# 130816_AriloRX_0_0.net
KiCad netlist of a schematic drawn in EAGLE
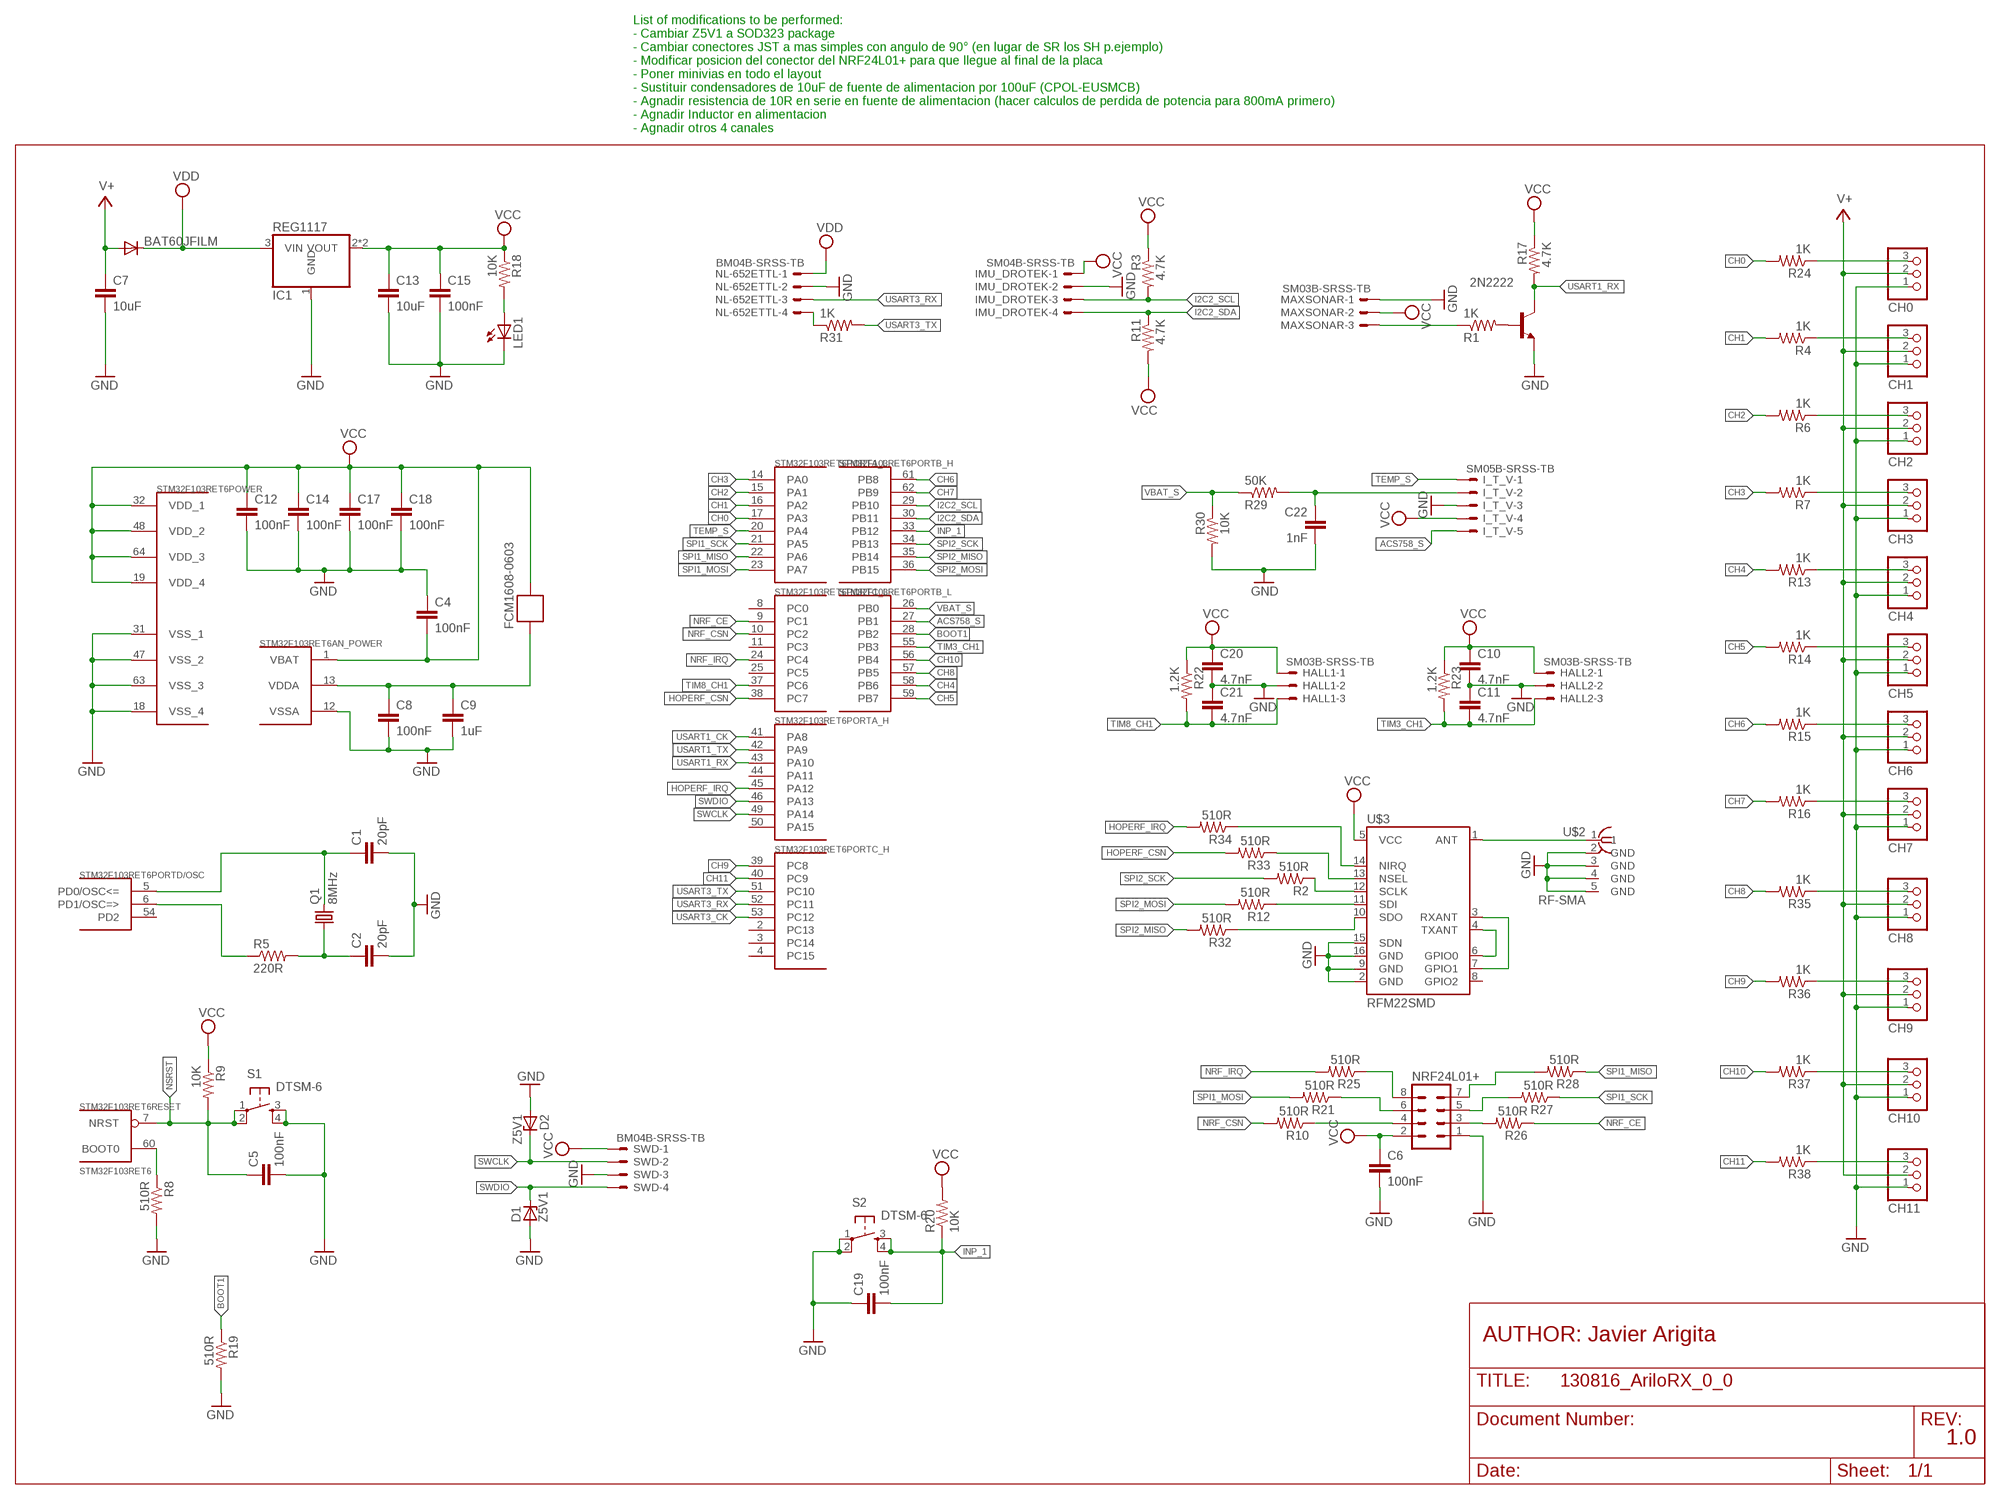
[diagram p0: schematic, sheet 1]

(export (version "E")
  (design (tool "Eeschema 10.0.6"))
  (components
    (comp (ref "2N2222")
      (value "MMBT2222ALT1-NPN-SOT23-BEC")
      (footprint "eagle-import:SOT23-BEC")
      (libsource (lib "eagle-import") (part "-NPN-SOT23-BECMMBT2222ALT1"))
    )
    (comp (ref "BAT60JFILM")
      (value "DIODE-SOD323-R")
      (footprint "eagle-import:SOD323-R")
      (libsource (lib "eagle-import") (part "DIODE-SOD323-R"))
    )
    (comp (ref "C1")
      (value "20pF")
      (footprint "eagle-import:C0805")
      (libsource (lib "eagle-import") (part "C-EUC0805"))
    )
    (comp (ref "C2")
      (value "20pF")
      (footprint "eagle-import:C0805")
      (libsource (lib "eagle-import") (part "C-EUC0805"))
    )
    (comp (ref "C4")
      (value "100nF")
      (footprint "eagle-import:C0805")
      (libsource (lib "eagle-import") (part "C-EUC0805"))
    )
    (comp (ref "C5")
      (value "100nF")
      (footprint "eagle-import:C0805")
      (libsource (lib "eagle-import") (part "C-EUC0805"))
    )
    (comp (ref "C6")
      (value "100nF")
      (footprint "eagle-import:C0805")
      (libsource (lib "eagle-import") (part "C-EUC0805"))
    )
    (comp (ref "C7")
      (value "10uF")
      (footprint "eagle-import:C3216")
      (libsource (lib "eagle-import") (part "resistor_C-EUC3216"))
    )
    (comp (ref "C8")
      (value "100nF")
      (footprint "eagle-import:C0805")
      (libsource (lib "eagle-import") (part "C-EUC0805"))
    )
    (comp (ref "C9")
      (value "1uF")
      (footprint "eagle-import:C3216")
      (libsource (lib "eagle-import") (part "resistor_C-EUC3216"))
    )
    (comp (ref "C10")
      (value "4.7nF")
      (footprint "eagle-import:C0805")
      (libsource (lib "eagle-import") (part "C-EUC0805"))
    )
    (comp (ref "C11")
      (value "4.7nF")
      (footprint "eagle-import:C0805")
      (libsource (lib "eagle-import") (part "C-EUC0805"))
    )
    (comp (ref "C12")
      (value "100nF")
      (footprint "eagle-import:C0805")
      (libsource (lib "eagle-import") (part "C-EUC0805"))
    )
    (comp (ref "C13")
      (value "10uF")
      (footprint "eagle-import:C3216")
      (libsource (lib "eagle-import") (part "resistor_C-EUC3216"))
    )
    (comp (ref "C14")
      (value "100nF")
      (footprint "eagle-import:C0805")
      (libsource (lib "eagle-import") (part "C-EUC0805"))
    )
    (comp (ref "C15")
      (value "100nF")
      (footprint "eagle-import:C0805")
      (libsource (lib "eagle-import") (part "C-EUC0805"))
    )
    (comp (ref "C17")
      (value "100nF")
      (footprint "eagle-import:C0805")
      (libsource (lib "eagle-import") (part "C-EUC0805"))
    )
    (comp (ref "C18")
      (value "100nF")
      (footprint "eagle-import:C0805")
      (libsource (lib "eagle-import") (part "C-EUC0805"))
    )
    (comp (ref "C19")
      (value "100nF")
      (footprint "eagle-import:C0805")
      (libsource (lib "eagle-import") (part "C-EUC0805"))
    )
    (comp (ref "C20")
      (value "4.7nF")
      (footprint "eagle-import:C0805")
      (libsource (lib "eagle-import") (part "C-EUC0805"))
    )
    (comp (ref "C21")
      (value "4.7nF")
      (footprint "eagle-import:C0805")
      (libsource (lib "eagle-import") (part "C-EUC0805"))
    )
    (comp (ref "C22")
      (value "1nF")
      (footprint "eagle-import:C0805")
      (libsource (lib "eagle-import") (part "C-EUC0805"))
    )
    (comp (ref "CH0")
      (value "PINHD-1X3")
      (footprint "eagle-import:1X03")
      (libsource (lib "eagle-import") (part "PINHD-1X3"))
    )
    (comp (ref "CH1")
      (value "PINHD-1X3")
      (footprint "eagle-import:1X03")
      (libsource (lib "eagle-import") (part "PINHD-1X3"))
    )
    (comp (ref "CH2")
      (value "PINHD-1X3")
      (footprint "eagle-import:1X03")
      (libsource (lib "eagle-import") (part "PINHD-1X3"))
    )
    (comp (ref "CH3")
      (value "PINHD-1X3")
      (footprint "eagle-import:1X03")
      (libsource (lib "eagle-import") (part "PINHD-1X3"))
    )
    (comp (ref "CH4")
      (value "PINHD-1X3")
      (footprint "eagle-import:1X03")
      (libsource (lib "eagle-import") (part "PINHD-1X3"))
    )
    (comp (ref "CH5")
      (value "PINHD-1X3")
      (footprint "eagle-import:1X03")
      (libsource (lib "eagle-import") (part "PINHD-1X3"))
    )
    (comp (ref "CH6")
      (value "PINHD-1X3")
      (footprint "eagle-import:1X03")
      (libsource (lib "eagle-import") (part "PINHD-1X3"))
    )
    (comp (ref "CH7")
      (value "PINHD-1X3")
      (footprint "eagle-import:1X03")
      (libsource (lib "eagle-import") (part "PINHD-1X3"))
    )
    (comp (ref "CH8")
      (value "PINHD-1X3")
      (footprint "eagle-import:1X03")
      (libsource (lib "eagle-import") (part "PINHD-1X3"))
    )
    (comp (ref "CH9")
      (value "PINHD-1X3")
      (footprint "eagle-import:1X03")
      (libsource (lib "eagle-import") (part "PINHD-1X3"))
    )
    (comp (ref "CH10")
      (value "PINHD-1X3")
      (footprint "eagle-import:1X03")
      (libsource (lib "eagle-import") (part "PINHD-1X3"))
    )
    (comp (ref "CH11")
      (value "PINHD-1X3")
      (footprint "eagle-import:1X03")
      (libsource (lib "eagle-import") (part "PINHD-1X3"))
    )
    (comp (ref "D1")
      (value "Z5V1")
      (footprint "eagle-import:SOD80C")
      (libsource (lib "eagle-import") (part "ZENER-DIODESOD80C"))
    )
    (comp (ref "D2")
      (value "Z5V1")
      (footprint "eagle-import:SOD80C")
      (libsource (lib "eagle-import") (part "ZENER-DIODESOD80C"))
    )
    (comp (ref "FCM1608-0603")
      (value "FERRITE-BEAD")
      (footprint "eagle-import:R0603")
      (libsource (lib "eagle-import") (part "FERRITE-BEAD"))
    )
    (comp (ref "HALL1")
      (value "SM03B-SRSS-TB")
      (footprint "eagle-import:SM03B-SRSS-TB")
      (libsource (lib "eagle-import") (part "?M03B-SRSS-TBS"))
    )
    (comp (ref "HALL2")
      (value "SM03B-SRSS-TB")
      (footprint "eagle-import:SM03B-SRSS-TB")
      (libsource (lib "eagle-import") (part "?M03B-SRSS-TBS"))
    )
    (comp (ref "IC1")
      (value "REG1117")
      (footprint "eagle-import:SOT223")
      (libsource (lib "eagle-import") (part "REG1117"))
    )
    (comp (ref "IMU_DROTEK")
      (value "SM04B-SRSS-TB")
      (footprint "eagle-import:SM04B-SRSS-TB")
      (libsource (lib "eagle-import") (part "?M04B-SRSS-TBS"))
    )
    (comp (ref "I_T_V")
      (value "SM05B-SRSS-TB")
      (footprint "eagle-import:SM05B-SRSS-TB")
      (libsource (lib "eagle-import") (part "?M05B-SRSS-TBS"))
    )
    (comp (ref "LED1")
      (value "LED0805")
      (footprint "eagle-import:CHIPLED_0805")
      (libsource (lib "eagle-import") (part "LED0805"))
    )
    (comp (ref "MAXSONAR")
      (value "SM03B-SRSS-TB")
      (footprint "eagle-import:SM03B-SRSS-TB")
      (libsource (lib "eagle-import") (part "?M03B-SRSS-TBS"))
    )
    (comp (ref "NL-652ETTL")
      (value "BM04B-SRSS-TB")
      (footprint "eagle-import:BM04B-SRSS-TB")
      (libsource (lib "eagle-import") (part "?M04B-SRSS-TBB"))
    )
    (comp (ref "NRF24L01+")
      (value "MA04-2")
      (footprint "eagle-import:MA04-2")
      (libsource (lib "eagle-import") (part "MA04-2"))
    )
    (comp (ref "Q1")
      (value "8MHz")
      (footprint "eagle-import:SM49")
      (libsource (lib "eagle-import") (part "CRYSTALSM49"))
    )
    (comp (ref "R1")
      (value "1K")
      (footprint "eagle-import:R0805")
      (libsource (lib "eagle-import") (part "RESISTOR0805"))
    )
    (comp (ref "R2")
      (value "510R")
      (footprint "eagle-import:R0805")
      (libsource (lib "eagle-import") (part "RESISTOR0805"))
    )
    (comp (ref "R3")
      (value "4.7K")
      (footprint "eagle-import:R0805")
      (libsource (lib "eagle-import") (part "RESISTOR0805"))
    )
    (comp (ref "R4")
      (value "1K")
      (footprint "eagle-import:R0805")
      (libsource (lib "eagle-import") (part "RESISTOR0805"))
    )
    (comp (ref "R5")
      (value "220R")
      (footprint "eagle-import:R0805")
      (libsource (lib "eagle-import") (part "RESISTOR0805"))
    )
    (comp (ref "R6")
      (value "1K")
      (footprint "eagle-import:R0805")
      (libsource (lib "eagle-import") (part "RESISTOR0805"))
    )
    (comp (ref "R7")
      (value "1K")
      (footprint "eagle-import:R0805")
      (libsource (lib "eagle-import") (part "RESISTOR0805"))
    )
    (comp (ref "R8")
      (value "510R")
      (footprint "eagle-import:R0805")
      (libsource (lib "eagle-import") (part "RESISTOR0805"))
    )
    (comp (ref "R9")
      (value "10K")
      (footprint "eagle-import:R0805")
      (libsource (lib "eagle-import") (part "RESISTOR0805"))
    )
    (comp (ref "R10")
      (value "510R")
      (footprint "eagle-import:R0805")
      (libsource (lib "eagle-import") (part "RESISTOR0805"))
    )
    (comp (ref "R11")
      (value "4.7K")
      (footprint "eagle-import:R0805")
      (libsource (lib "eagle-import") (part "RESISTOR0805"))
    )
    (comp (ref "R12")
      (value "510R")
      (footprint "eagle-import:R0805")
      (libsource (lib "eagle-import") (part "RESISTOR0805"))
    )
    (comp (ref "R13")
      (value "1K")
      (footprint "eagle-import:R0805")
      (libsource (lib "eagle-import") (part "RESISTOR0805"))
    )
    (comp (ref "R14")
      (value "1K")
      (footprint "eagle-import:R0805")
      (libsource (lib "eagle-import") (part "RESISTOR0805"))
    )
    (comp (ref "R15")
      (value "1K")
      (footprint "eagle-import:R0805")
      (libsource (lib "eagle-import") (part "RESISTOR0805"))
    )
    (comp (ref "R16")
      (value "1K")
      (footprint "eagle-import:R0805")
      (libsource (lib "eagle-import") (part "RESISTOR0805"))
    )
    (comp (ref "R17")
      (value "4.7K")
      (footprint "eagle-import:R0805")
      (libsource (lib "eagle-import") (part "RESISTOR0805"))
    )
    (comp (ref "R18")
      (value "10K")
      (footprint "eagle-import:R0805")
      (libsource (lib "eagle-import") (part "RESISTOR0805"))
    )
    (comp (ref "R19")
      (value "510R")
      (footprint "eagle-import:R0805")
      (libsource (lib "eagle-import") (part "RESISTOR0805"))
    )
    (comp (ref "R20")
      (value "10K")
      (footprint "eagle-import:R0805")
      (libsource (lib "eagle-import") (part "RESISTOR0805"))
    )
    (comp (ref "R21")
      (value "510R")
      (footprint "eagle-import:R0805")
      (libsource (lib "eagle-import") (part "RESISTOR0805"))
    )
    (comp (ref "R22")
      (value "1.2K")
      (footprint "eagle-import:R0805")
      (libsource (lib "eagle-import") (part "RESISTOR0805"))
    )
    (comp (ref "R23")
      (value "1.2K")
      (footprint "eagle-import:R0805")
      (libsource (lib "eagle-import") (part "RESISTOR0805"))
    )
    (comp (ref "R24")
      (value "1K")
      (footprint "eagle-import:R0805")
      (libsource (lib "eagle-import") (part "RESISTOR0805"))
    )
    (comp (ref "R25")
      (value "510R")
      (footprint "eagle-import:R0805")
      (libsource (lib "eagle-import") (part "RESISTOR0805"))
    )
    (comp (ref "R26")
      (value "510R")
      (footprint "eagle-import:R0805")
      (libsource (lib "eagle-import") (part "RESISTOR0805"))
    )
    (comp (ref "R27")
      (value "510R")
      (footprint "eagle-import:R0805")
      (libsource (lib "eagle-import") (part "RESISTOR0805"))
    )
    (comp (ref "R28")
      (value "510R")
      (footprint "eagle-import:R0805")
      (libsource (lib "eagle-import") (part "RESISTOR0805"))
    )
    (comp (ref "R29")
      (value "50K")
      (footprint "eagle-import:R0805")
      (libsource (lib "eagle-import") (part "RESISTOR0805"))
    )
    (comp (ref "R30")
      (value "10K")
      (footprint "eagle-import:R0805")
      (libsource (lib "eagle-import") (part "RESISTOR0805"))
    )
    (comp (ref "R31")
      (value "1K")
      (footprint "eagle-import:R0805")
      (libsource (lib "eagle-import") (part "RESISTOR0805"))
    )
    (comp (ref "R32")
      (value "510R")
      (footprint "eagle-import:R0805")
      (libsource (lib "eagle-import") (part "RESISTOR0805"))
    )
    (comp (ref "R33")
      (value "510R")
      (footprint "eagle-import:R0805")
      (libsource (lib "eagle-import") (part "RESISTOR0805"))
    )
    (comp (ref "R34")
      (value "510R")
      (footprint "eagle-import:R0805")
      (libsource (lib "eagle-import") (part "RESISTOR0805"))
    )
    (comp (ref "R35")
      (value "1K")
      (footprint "eagle-import:R0805")
      (libsource (lib "eagle-import") (part "RESISTOR0805"))
    )
    (comp (ref "R36")
      (value "1K")
      (footprint "eagle-import:R0805")
      (libsource (lib "eagle-import") (part "RESISTOR0805"))
    )
    (comp (ref "R37")
      (value "1K")
      (footprint "eagle-import:R0805")
      (libsource (lib "eagle-import") (part "RESISTOR0805"))
    )
    (comp (ref "R38")
      (value "1K")
      (footprint "eagle-import:R0805")
      (libsource (lib "eagle-import") (part "RESISTOR0805"))
    )
    (comp (ref "S1")
      (value "DTSM-6")
      (footprint "eagle-import:DTSM-6")
      (libsource (lib "eagle-import") (part "DTSM-6"))
    )
    (comp (ref "S2")
      (value "DTSM-6")
      (footprint "eagle-import:DTSM-6")
      (libsource (lib "eagle-import") (part "DTSM-6"))
    )
    (comp (ref "STM32F103RET6")
      (value "STM32F103RET6")
      (footprint "eagle-import:TQFP64")
      (libsource (lib "eagle-import") (part "STM32F10XRXT6"))
    )
    (comp (ref "SWD")
      (value "BM04B-SRSS-TB")
      (footprint "eagle-import:BM04B-SRSS-TB")
      (libsource (lib "eagle-import") (part "?M04B-SRSS-TBB"))
    )
    (comp (ref "U$2")
      (value "RF-SMA")
      (footprint "eagle-import:BU-SMA-H")
      (libsource (lib "eagle-import") (part "RF-SMA"))
    )
    (comp (ref "U$3")
      (value "RFM22SMD")
      (footprint "eagle-import:RFM22-XXX-S2")
      (libsource (lib "eagle-import") (part "RFM22SMD"))
    )
  )
  (nets
    (net (code "1") (name "ACS758_S") (class "Default")
      (node (ref "I_T_V") (pin "5") (pinfunction "S_5") (pintype "passive"))
      (node (ref "STM32F103RET6") (pin "27") (pinfunction "PB1_27") (pintype "bidirectional"))
    )
    (net (code "2") (name "BOOT1") (class "Default")
      (node (ref "R19") (pin "1") (pinfunction "1_1") (pintype "passive"))
      (node (ref "STM32F103RET6") (pin "28") (pinfunction "PB2_28") (pintype "bidirectional"))
    )
    (net (code "3") (name "CH0") (class "Default")
      (node (ref "R24") (pin "2") (pinfunction "2_2") (pintype "passive"))
      (node (ref "STM32F103RET6") (pin "17") (pinfunction "PA3_17") (pintype "bidirectional"))
    )
    (net (code "4") (name "CH1") (class "Default")
      (node (ref "R4") (pin "2") (pinfunction "2_2") (pintype "passive"))
      (node (ref "STM32F103RET6") (pin "16") (pinfunction "PA2_16") (pintype "bidirectional"))
    )
    (net (code "5") (name "CH2") (class "Default")
      (node (ref "R6") (pin "2") (pinfunction "2_2") (pintype "passive"))
      (node (ref "STM32F103RET6") (pin "15") (pinfunction "PA1_15") (pintype "bidirectional"))
    )
    (net (code "6") (name "CH3") (class "Default")
      (node (ref "R7") (pin "2") (pinfunction "2_2") (pintype "passive"))
      (node (ref "STM32F103RET6") (pin "14") (pinfunction "PA0_14") (pintype "bidirectional"))
    )
    (net (code "7") (name "CH4") (class "Default")
      (node (ref "R13") (pin "2") (pinfunction "2_2") (pintype "passive"))
      (node (ref "STM32F103RET6") (pin "58") (pinfunction "PB6_58") (pintype "bidirectional"))
    )
    (net (code "8") (name "CH5") (class "Default")
      (node (ref "R14") (pin "2") (pinfunction "2_2") (pintype "passive"))
      (node (ref "STM32F103RET6") (pin "59") (pinfunction "PB7_59") (pintype "bidirectional"))
    )
    (net (code "9") (name "CH6") (class "Default")
      (node (ref "R15") (pin "2") (pinfunction "2_2") (pintype "passive"))
      (node (ref "STM32F103RET6") (pin "61") (pinfunction "PB8_61") (pintype "bidirectional"))
    )
    (net (code "10") (name "CH7") (class "Default")
      (node (ref "R16") (pin "2") (pinfunction "2_2") (pintype "passive"))
      (node (ref "STM32F103RET6") (pin "62") (pinfunction "PB9_62") (pintype "bidirectional"))
    )
    (net (code "11") (name "CH8") (class "Default")
      (node (ref "R35") (pin "2") (pinfunction "2_2") (pintype "passive"))
      (node (ref "STM32F103RET6") (pin "57") (pinfunction "PB5_57") (pintype "bidirectional"))
    )
    (net (code "12") (name "CH9") (class "Default")
      (node (ref "R36") (pin "2") (pinfunction "2_2") (pintype "passive"))
      (node (ref "STM32F103RET6") (pin "39") (pinfunction "PC8_39") (pintype "bidirectional"))
    )
    (net (code "13") (name "CH10") (class "Default")
      (node (ref "R37") (pin "2") (pinfunction "2_2") (pintype "passive"))
      (node (ref "STM32F103RET6") (pin "56") (pinfunction "PB4_56") (pintype "bidirectional"))
    )
    (net (code "14") (name "CH11") (class "Default")
      (node (ref "R38") (pin "2") (pinfunction "2_2") (pintype "passive"))
      (node (ref "STM32F103RET6") (pin "40") (pinfunction "PC9_40") (pintype "bidirectional"))
    )
    (net (code "15") (name "GND") (class "Default")
      (node (ref "2N2222") (pin "E") (pinfunction "E_E") (pintype "passive"))
      (node (ref "C1") (pin "2") (pinfunction "2_2") (pintype "passive"))
      (node (ref "C10") (pin "2") (pinfunction "2_2") (pintype "passive"))
      (node (ref "C11") (pin "1") (pinfunction "1_1") (pintype "passive"))
      (node (ref "C12") (pin "2") (pinfunction "2_2") (pintype "passive"))
      (node (ref "C13") (pin "2") (pinfunction "2_2") (pintype "passive"))
      (node (ref "C14") (pin "2") (pinfunction "2_2") (pintype "passive"))
      (node (ref "C15") (pin "2") (pinfunction "2_2") (pintype "passive"))
      (node (ref "C17") (pin "2") (pinfunction "2_2") (pintype "passive"))
      (node (ref "C18") (pin "2") (pinfunction "2_2") (pintype "passive"))
      (node (ref "C19") (pin "1") (pinfunction "1_1") (pintype "passive"))
      (node (ref "C2") (pin "2") (pinfunction "2_2") (pintype "passive"))
      (node (ref "C20") (pin "2") (pinfunction "2_2") (pintype "passive"))
      (node (ref "C21") (pin "1") (pinfunction "1_1") (pintype "passive"))
      (node (ref "C22") (pin "2") (pinfunction "2_2") (pintype "passive"))
      (node (ref "C4") (pin "1") (pinfunction "1_1") (pintype "passive"))
      (node (ref "C5") (pin "2") (pinfunction "2_2") (pintype "passive"))
      (node (ref "C6") (pin "2") (pinfunction "2_2") (pintype "passive"))
      (node (ref "C7") (pin "2") (pinfunction "2_2") (pintype "passive"))
      (node (ref "C8") (pin "2") (pinfunction "2_2") (pintype "passive"))
      (node (ref "C9") (pin "2") (pinfunction "2_2") (pintype "passive"))
      (node (ref "CH0") (pin "1") (pinfunction "1_1") (pintype "passive"))
      (node (ref "CH1") (pin "1") (pinfunction "1_1") (pintype "passive"))
      (node (ref "CH10") (pin "1") (pinfunction "1_1") (pintype "passive"))
      (node (ref "CH11") (pin "1") (pinfunction "1_1") (pintype "passive"))
      (node (ref "CH2") (pin "1") (pinfunction "1_1") (pintype "passive"))
      (node (ref "CH3") (pin "1") (pinfunction "1_1") (pintype "passive"))
      (node (ref "CH4") (pin "1") (pinfunction "1_1") (pintype "passive"))
      (node (ref "CH5") (pin "1") (pinfunction "1_1") (pintype "passive"))
      (node (ref "CH6") (pin "1") (pinfunction "1_1") (pintype "passive"))
      (node (ref "CH7") (pin "1") (pinfunction "1_1") (pintype "passive"))
      (node (ref "CH8") (pin "1") (pinfunction "1_1") (pintype "passive"))
      (node (ref "CH9") (pin "1") (pinfunction "1_1") (pintype "passive"))
      (node (ref "D1") (pin "A") (pinfunction "A_A") (pintype "passive"))
      (node (ref "D2") (pin "A") (pinfunction "A_A") (pintype "passive"))
      (node (ref "HALL1") (pin "2") (pinfunction "S_2") (pintype "passive"))
      (node (ref "HALL2") (pin "2") (pinfunction "S_2") (pintype "passive"))
      (node (ref "IC1") (pin "1") (pinfunction "GND_1") (pintype "power_in"))
      (node (ref "IMU_DROTEK") (pin "2") (pinfunction "S_2") (pintype "passive"))
      (node (ref "I_T_V") (pin "3") (pinfunction "S_3") (pintype "passive"))
      (node (ref "LED1") (pin "C") (pinfunction "C_C") (pintype "passive"))
      (node (ref "MAXSONAR") (pin "1") (pinfunction "S_1") (pintype "passive"))
      (node (ref "NL-652ETTL") (pin "2") (pinfunction "S_2") (pintype "passive"))
      (node (ref "NRF24L01+") (pin "1") (pinfunction "1_1") (pintype "passive"))
      (node (ref "R19") (pin "2") (pinfunction "2_2") (pintype "passive"))
      (node (ref "R30") (pin "2") (pinfunction "2_2") (pintype "passive"))
      (node (ref "R8") (pin "2") (pinfunction "2_2") (pintype "passive"))
      (node (ref "S1") (pin "3") (pinfunction "3_3") (pintype "passive"))
      (node (ref "S1") (pin "4") (pinfunction "4_4") (pintype "passive"))
      (node (ref "S2") (pin "1") (pinfunction "1_1") (pintype "passive"))
      (node (ref "S2") (pin "2") (pinfunction "2_2") (pintype "passive"))
      (node (ref "STM32F103RET6") (pin "12") (pinfunction "VSSA_12") (pintype "power_in"))
      (node (ref "STM32F103RET6") (pin "18") (pinfunction "VSS_4_18") (pintype "power_in"))
      (node (ref "STM32F103RET6") (pin "31") (pinfunction "VSS_1_31") (pintype "power_in"))
      (node (ref "STM32F103RET6") (pin "47") (pinfunction "VSS_2_47") (pintype "power_in"))
      (node (ref "STM32F103RET6") (pin "63") (pinfunction "VSS_3_63") (pintype "power_in"))
      (node (ref "SWD") (pin "3") (pinfunction "S_3") (pintype "passive"))
      (node (ref "U$2") (pin "2") (pinfunction "GND_2") (pintype "power_in"))
      (node (ref "U$2") (pin "3") (pinfunction "GND_3") (pintype "bidirectional"))
      (node (ref "U$2") (pin "4") (pinfunction "GND_4") (pintype "bidirectional"))
      (node (ref "U$2") (pin "5") (pinfunction "GND_5") (pintype "bidirectional"))
      (node (ref "U$3") (pin "15") (pinfunction "SDN_15") (pintype "input"))
      (node (ref "U$3") (pin "16") (pinfunction "GND_16") (pintype "power_in"))
      (node (ref "U$3") (pin "2") (pinfunction "GND_2") (pintype "power_in"))
      (node (ref "U$3") (pin "9") (pinfunction "GND_9") (pintype "power_in"))
    )
    (net (code "16") (name "HOPERF_CSN") (class "Default")
      (node (ref "R33") (pin "2") (pinfunction "2_2") (pintype "passive"))
      (node (ref "STM32F103RET6") (pin "38") (pinfunction "PC7_38") (pintype "bidirectional"))
    )
    (net (code "17") (name "HOPERF_IRQ") (class "Default")
      (node (ref "R34") (pin "2") (pinfunction "2_2") (pintype "passive"))
      (node (ref "STM32F103RET6") (pin "45") (pinfunction "PA12_45") (pintype "bidirectional"))
    )
    (net (code "18") (name "I2C2_SCL") (class "Default")
      (node (ref "IMU_DROTEK") (pin "3") (pinfunction "S_3") (pintype "passive"))
      (node (ref "R3") (pin "2") (pinfunction "2_2") (pintype "passive"))
      (node (ref "STM32F103RET6") (pin "29") (pinfunction "PB10_29") (pintype "bidirectional"))
    )
    (net (code "19") (name "I2C2_SDA") (class "Default")
      (node (ref "IMU_DROTEK") (pin "4") (pinfunction "S_4") (pintype "passive"))
      (node (ref "R11") (pin "1") (pinfunction "1_1") (pintype "passive"))
      (node (ref "STM32F103RET6") (pin "30") (pinfunction "PB11_30") (pintype "bidirectional"))
    )
    (net (code "20") (name "INP_1") (class "Default")
      (node (ref "C19") (pin "2") (pinfunction "2_2") (pintype "passive"))
      (node (ref "R20") (pin "1") (pinfunction "1_1") (pintype "passive"))
      (node (ref "S2") (pin "3") (pinfunction "3_3") (pintype "passive"))
      (node (ref "S2") (pin "4") (pinfunction "4_4") (pintype "passive"))
      (node (ref "STM32F103RET6") (pin "33") (pinfunction "PB12_33") (pintype "bidirectional"))
    )
    (net (code "21") (name "NRF_CE") (class "Default")
      (node (ref "R26") (pin "1") (pinfunction "1_1") (pintype "passive"))
      (node (ref "STM32F103RET6") (pin "9") (pinfunction "PC1_9") (pintype "bidirectional"))
    )
    (net (code "22") (name "NRF_CSN") (class "Default")
      (node (ref "R10") (pin "2") (pinfunction "2_2") (pintype "passive"))
      (node (ref "STM32F103RET6") (pin "10") (pinfunction "PC2_10") (pintype "bidirectional"))
    )
    (net (code "23") (name "NRF_IRQ") (class "Default")
      (node (ref "R25") (pin "2") (pinfunction "2_2") (pintype "passive"))
      (node (ref "STM32F103RET6") (pin "24") (pinfunction "PC4_24") (pintype "bidirectional"))
    )
    (net (code "24") (name "NSRST") (class "Default")
      (node (ref "C5") (pin "1") (pinfunction "1_1") (pintype "passive"))
      (node (ref "R9") (pin "2") (pinfunction "2_2") (pintype "passive"))
      (node (ref "S1") (pin "1") (pinfunction "1_1") (pintype "passive"))
      (node (ref "S1") (pin "2") (pinfunction "2_2") (pintype "passive"))
      (node (ref "STM32F103RET6") (pin "7") (pinfunction "NRST_7") (pintype "input"))
    )
    (net (code "25") (name "Net-(2N2222-PadB)") (class "Default")
      (node (ref "2N2222") (pin "B") (pinfunction "B_B") (pintype "passive"))
      (node (ref "R1") (pin "2") (pinfunction "2_2") (pintype "passive"))
    )
    (net (code "26") (name "Net-(C2-Pad1)") (class "Default")
      (node (ref "C2") (pin "1") (pinfunction "1_1") (pintype "passive"))
      (node (ref "Q1") (pin "1") (pinfunction "1_1") (pintype "passive"))
      (node (ref "R5") (pin "2") (pinfunction "2_2") (pintype "passive"))
    )
    (net (code "27") (name "Net-(CH0-Pad3)") (class "Default")
      (node (ref "CH0") (pin "3") (pinfunction "3_3") (pintype "passive"))
      (node (ref "R24") (pin "1") (pinfunction "1_1") (pintype "passive"))
    )
    (net (code "28") (name "Net-(CH1-Pad3)") (class "Default")
      (node (ref "CH1") (pin "3") (pinfunction "3_3") (pintype "passive"))
      (node (ref "R4") (pin "1") (pinfunction "1_1") (pintype "passive"))
    )
    (net (code "29") (name "Net-(CH2-Pad3)") (class "Default")
      (node (ref "CH2") (pin "3") (pinfunction "3_3") (pintype "passive"))
      (node (ref "R6") (pin "1") (pinfunction "1_1") (pintype "passive"))
    )
    (net (code "30") (name "Net-(CH3-Pad3)") (class "Default")
      (node (ref "CH3") (pin "3") (pinfunction "3_3") (pintype "passive"))
      (node (ref "R7") (pin "1") (pinfunction "1_1") (pintype "passive"))
    )
    (net (code "31") (name "Net-(CH4-Pad3)") (class "Default")
      (node (ref "CH4") (pin "3") (pinfunction "3_3") (pintype "passive"))
      (node (ref "R13") (pin "1") (pinfunction "1_1") (pintype "passive"))
    )
    (net (code "32") (name "Net-(CH5-Pad3)") (class "Default")
      (node (ref "CH5") (pin "3") (pinfunction "3_3") (pintype "passive"))
      (node (ref "R14") (pin "1") (pinfunction "1_1") (pintype "passive"))
    )
    (net (code "33") (name "Net-(CH6-Pad3)") (class "Default")
      (node (ref "CH6") (pin "3") (pinfunction "3_3") (pintype "passive"))
      (node (ref "R15") (pin "1") (pinfunction "1_1") (pintype "passive"))
    )
    (net (code "34") (name "Net-(CH7-Pad3)") (class "Default")
      (node (ref "CH7") (pin "3") (pinfunction "3_3") (pintype "passive"))
      (node (ref "R16") (pin "1") (pinfunction "1_1") (pintype "passive"))
    )
    (net (code "35") (name "Net-(CH8-Pad3)") (class "Default")
      (node (ref "CH8") (pin "3") (pinfunction "3_3") (pintype "passive"))
      (node (ref "R35") (pin "1") (pinfunction "1_1") (pintype "passive"))
    )
    (net (code "36") (name "Net-(CH9-Pad3)") (class "Default")
      (node (ref "CH9") (pin "3") (pinfunction "3_3") (pintype "passive"))
      (node (ref "R36") (pin "1") (pinfunction "1_1") (pintype "passive"))
    )
    (net (code "37") (name "Net-(CH10-Pad3)") (class "Default")
      (node (ref "CH10") (pin "3") (pinfunction "3_3") (pintype "passive"))
      (node (ref "R37") (pin "1") (pinfunction "1_1") (pintype "passive"))
    )
    (net (code "38") (name "Net-(CH11-Pad3)") (class "Default")
      (node (ref "CH11") (pin "3") (pinfunction "3_3") (pintype "passive"))
      (node (ref "R38") (pin "1") (pinfunction "1_1") (pintype "passive"))
    )
    (net (code "39") (name "Net-(FCM1608-0603-P$2)") (class "Default")
      (node (ref "C8") (pin "1") (pinfunction "1_1") (pintype "passive"))
      (node (ref "C9") (pin "1") (pinfunction "1_1") (pintype "passive"))
      (node (ref "FCM1608-0603") (pin "2") (pinfunction "P$2_2") (pintype "bidirectional"))
      (node (ref "STM32F103RET6") (pin "13") (pinfunction "VDDA_13") (pintype "power_in"))
    )
    (net (code "40") (name "Net-(I_T_VB-S)") (class "Default")
      (node (ref "C22") (pin "1") (pinfunction "1_1") (pintype "passive"))
      (node (ref "I_T_V") (pin "2") (pinfunction "S_2") (pintype "passive"))
      (node (ref "R29") (pin "2") (pinfunction "2_2") (pintype "passive"))
    )
    (net (code "41") (name "Net-(LED1-PadA)") (class "Default")
      (node (ref "LED1") (pin "A") (pinfunction "A_A") (pintype "passive"))
      (node (ref "R18") (pin "2") (pinfunction "2_2") (pintype "passive"))
    )
    (net (code "42") (name "Net-(MAXSONARC-S)") (class "Default")
      (node (ref "MAXSONAR") (pin "3") (pinfunction "S_3") (pintype "passive"))
      (node (ref "R1") (pin "1") (pinfunction "1_1") (pintype "passive"))
    )
    (net (code "43") (name "Net-(NL-652ETTLD-S)") (class "Default")
      (node (ref "NL-652ETTL") (pin "4") (pinfunction "S_4") (pintype "passive"))
      (node (ref "R31") (pin "1") (pinfunction "1_1") (pintype "passive"))
    )
    (net (code "44") (name "Net-(NRF24L01+-Pad3)") (class "Default")
      (node (ref "NRF24L01+") (pin "3") (pinfunction "3_3") (pintype "passive"))
      (node (ref "R26") (pin "2") (pinfunction "2_2") (pintype "passive"))
    )
    (net (code "45") (name "Net-(NRF24L01+-Pad4)") (class "Default")
      (node (ref "NRF24L01+") (pin "4") (pinfunction "4_4") (pintype "passive"))
      (node (ref "R10") (pin "1") (pinfunction "1_1") (pintype "passive"))
    )
    (net (code "46") (name "Net-(NRF24L01+-Pad5)") (class "Default")
      (node (ref "NRF24L01+") (pin "5") (pinfunction "5_5") (pintype "passive"))
      (node (ref "R27") (pin "2") (pinfunction "2_2") (pintype "passive"))
    )
    (net (code "47") (name "Net-(NRF24L01+-Pad6)") (class "Default")
      (node (ref "NRF24L01+") (pin "6") (pinfunction "6_6") (pintype "passive"))
      (node (ref "R21") (pin "1") (pinfunction "1_1") (pintype "passive"))
    )
    (net (code "48") (name "Net-(NRF24L01+-Pad7)") (class "Default")
      (node (ref "NRF24L01+") (pin "7") (pinfunction "7_7") (pintype "passive"))
      (node (ref "R28") (pin "2") (pinfunction "2_2") (pintype "passive"))
    )
    (net (code "49") (name "Net-(NRF24L01+-Pad8)") (class "Default")
      (node (ref "NRF24L01+") (pin "8") (pinfunction "8_8") (pintype "passive"))
      (node (ref "R25") (pin "1") (pinfunction "1_1") (pintype "passive"))
    )
    (net (code "50") (name "Net-(STM32F103RET6H-PD0{slash}OSC<=)") (class "Default")
      (node (ref "C1") (pin "1") (pinfunction "1_1") (pintype "passive"))
      (node (ref "Q1") (pin "2") (pinfunction "2_2") (pintype "passive"))
      (node (ref "STM32F103RET6") (pin "5") (pinfunction "PD0/OSC<=_5") (pintype "bidirectional"))
    )
    (net (code "51") (name "Net-(STM32F103RET6H-PD1{slash}OSC=>)") (class "Default")
      (node (ref "R5") (pin "1") (pinfunction "1_1") (pintype "passive"))
      (node (ref "STM32F103RET6") (pin "6") (pinfunction "PD1/OSC=>_6") (pintype "bidirectional"))
    )
    (net (code "52") (name "Net-(STM32F103RET6J-BOOT0)") (class "Default")
      (node (ref "R8") (pin "1") (pinfunction "1_1") (pintype "passive"))
      (node (ref "STM32F103RET6") (pin "60") (pinfunction "BOOT0_60") (pintype "input"))
    )
    (net (code "53") (name "Net-(U$3-ANT)") (class "Default")
      (node (ref "U$2") (pin "1") (pinfunction "1_1") (pintype "passive"))
      (node (ref "U$3") (pin "1") (pinfunction "ANT_1") (pintype "bidirectional"))
    )
    (net (code "54") (name "Net-(U$3-GPIO0)") (class "Default")
      (node (ref "U$3") (pin "4") (pinfunction "TXANT_4") (pintype "input"))
      (node (ref "U$3") (pin "6") (pinfunction "GPIO0_6") (pintype "bidirectional"))
    )
    (net (code "55") (name "Net-(U$3-GPIO1)") (class "Default")
      (node (ref "U$3") (pin "3") (pinfunction "RXANT_3") (pintype "input"))
      (node (ref "U$3") (pin "7") (pinfunction "GPIO1_7") (pintype "bidirectional"))
    )
    (net (code "56") (name "Net-(U$3-NIRQ)") (class "Default")
      (node (ref "R34") (pin "1") (pinfunction "1_1") (pintype "passive"))
      (node (ref "U$3") (pin "14") (pinfunction "NIRQ_14") (pintype "output"))
    )
    (net (code "57") (name "Net-(U$3-NSEL)") (class "Default")
      (node (ref "R33") (pin "1") (pinfunction "1_1") (pintype "passive"))
      (node (ref "U$3") (pin "13") (pinfunction "NSEL_13") (pintype "input"))
    )
    (net (code "58") (name "Net-(U$3-SCLK)") (class "Default")
      (node (ref "R2") (pin "1") (pinfunction "1_1") (pintype "passive"))
      (node (ref "U$3") (pin "12") (pinfunction "SCLK_12") (pintype "input"))
    )
    (net (code "59") (name "Net-(U$3-SDI)") (class "Default")
      (node (ref "R12") (pin "1") (pinfunction "1_1") (pintype "passive"))
      (node (ref "U$3") (pin "11") (pinfunction "SDI_11") (pintype "input"))
    )
    (net (code "60") (name "Net-(U$3-SDO)") (class "Default")
      (node (ref "R32") (pin "1") (pinfunction "1_1") (pintype "passive"))
      (node (ref "U$3") (pin "10") (pinfunction "SDO_10") (pintype "output"))
    )
    (net (code "61") (name "SPI1_MISO") (class "Default")
      (node (ref "R28") (pin "1") (pinfunction "1_1") (pintype "passive"))
      (node (ref "STM32F103RET6") (pin "22") (pinfunction "PA6_22") (pintype "bidirectional"))
    )
    (net (code "62") (name "SPI1_MOSI") (class "Default")
      (node (ref "R21") (pin "2") (pinfunction "2_2") (pintype "passive"))
      (node (ref "STM32F103RET6") (pin "23") (pinfunction "PA7_23") (pintype "bidirectional"))
    )
    (net (code "63") (name "SPI1_SCK") (class "Default")
      (node (ref "R27") (pin "1") (pinfunction "1_1") (pintype "passive"))
      (node (ref "STM32F103RET6") (pin "21") (pinfunction "PA5_21") (pintype "bidirectional"))
    )
    (net (code "64") (name "SPI2_MISO") (class "Default")
      (node (ref "R32") (pin "2") (pinfunction "2_2") (pintype "passive"))
      (node (ref "STM32F103RET6") (pin "35") (pinfunction "PB14_35") (pintype "bidirectional"))
    )
    (net (code "65") (name "SPI2_MOSI") (class "Default")
      (node (ref "R12") (pin "2") (pinfunction "2_2") (pintype "passive"))
      (node (ref "STM32F103RET6") (pin "36") (pinfunction "PB15_36") (pintype "bidirectional"))
    )
    (net (code "66") (name "SPI2_SCK") (class "Default")
      (node (ref "R2") (pin "2") (pinfunction "2_2") (pintype "passive"))
      (node (ref "STM32F103RET6") (pin "34") (pinfunction "PB13_34") (pintype "bidirectional"))
    )
    (net (code "67") (name "SWCLK") (class "Default")
      (node (ref "D2") (pin "C") (pinfunction "C_C") (pintype "passive"))
      (node (ref "STM32F103RET6") (pin "49") (pinfunction "PA14_49") (pintype "bidirectional"))
      (node (ref "SWD") (pin "2") (pinfunction "S_2") (pintype "passive"))
    )
    (net (code "68") (name "SWDIO") (class "Default")
      (node (ref "D1") (pin "C") (pinfunction "C_C") (pintype "passive"))
      (node (ref "STM32F103RET6") (pin "46") (pinfunction "PA13_46") (pintype "bidirectional"))
      (node (ref "SWD") (pin "4") (pinfunction "S_4") (pintype "passive"))
    )
    (net (code "69") (name "TEMP_S") (class "Default")
      (node (ref "I_T_V") (pin "1") (pinfunction "S_1") (pintype "passive"))
      (node (ref "STM32F103RET6") (pin "20") (pinfunction "PA4_20") (pintype "bidirectional"))
    )
    (net (code "70") (name "TIM3_CH1") (class "Default")
      (node (ref "C11") (pin "2") (pinfunction "2_2") (pintype "passive"))
      (node (ref "HALL2") (pin "3") (pinfunction "S_3") (pintype "passive"))
      (node (ref "R23") (pin "2") (pinfunction "2_2") (pintype "passive"))
      (node (ref "STM32F103RET6") (pin "55") (pinfunction "PB3_55") (pintype "bidirectional"))
    )
    (net (code "71") (name "TIM8_CH1") (class "Default")
      (node (ref "C21") (pin "2") (pinfunction "2_2") (pintype "passive"))
      (node (ref "HALL1") (pin "3") (pinfunction "S_3") (pintype "passive"))
      (node (ref "R22") (pin "2") (pinfunction "2_2") (pintype "passive"))
      (node (ref "STM32F103RET6") (pin "37") (pinfunction "PC6_37") (pintype "bidirectional"))
    )
    (net (code "72") (name "USART1_CK") (class "Default")
      (node (ref "STM32F103RET6") (pin "41") (pinfunction "PA8_41") (pintype "bidirectional"))
    )
    (net (code "73") (name "USART1_RX") (class "Default")
      (node (ref "2N2222") (pin "C") (pinfunction "C_C") (pintype "passive"))
      (node (ref "R17") (pin "2") (pinfunction "2_2") (pintype "passive"))
      (node (ref "STM32F103RET6") (pin "43") (pinfunction "PA10_43") (pintype "bidirectional"))
    )
    (net (code "74") (name "USART1_TX") (class "Default")
      (node (ref "STM32F103RET6") (pin "42") (pinfunction "PA9_42") (pintype "bidirectional"))
    )
    (net (code "75") (name "USART3_CK") (class "Default")
      (node (ref "STM32F103RET6") (pin "53") (pinfunction "PC12_53") (pintype "bidirectional"))
    )
    (net (code "76") (name "USART3_RX") (class "Default")
      (node (ref "NL-652ETTL") (pin "3") (pinfunction "S_3") (pintype "passive"))
      (node (ref "STM32F103RET6") (pin "52") (pinfunction "PC11_52") (pintype "bidirectional"))
    )
    (net (code "77") (name "USART3_TX") (class "Default")
      (node (ref "R31") (pin "2") (pinfunction "2_2") (pintype "passive"))
      (node (ref "STM32F103RET6") (pin "51") (pinfunction "PC10_51") (pintype "bidirectional"))
    )
    (net (code "78") (name "V+") (class "Default")
      (node (ref "BAT60JFILM") (pin "A") (pinfunction "A_A") (pintype "passive"))
      (node (ref "C7") (pin "1") (pinfunction "1_1") (pintype "passive"))
      (node (ref "CH0") (pin "2") (pinfunction "2_2") (pintype "passive"))
      (node (ref "CH1") (pin "2") (pinfunction "2_2") (pintype "passive"))
      (node (ref "CH10") (pin "2") (pinfunction "2_2") (pintype "passive"))
      (node (ref "CH11") (pin "2") (pinfunction "2_2") (pintype "passive"))
      (node (ref "CH2") (pin "2") (pinfunction "2_2") (pintype "passive"))
      (node (ref "CH3") (pin "2") (pinfunction "2_2") (pintype "passive"))
      (node (ref "CH4") (pin "2") (pinfunction "2_2") (pintype "passive"))
      (node (ref "CH5") (pin "2") (pinfunction "2_2") (pintype "passive"))
      (node (ref "CH6") (pin "2") (pinfunction "2_2") (pintype "passive"))
      (node (ref "CH7") (pin "2") (pinfunction "2_2") (pintype "passive"))
      (node (ref "CH8") (pin "2") (pinfunction "2_2") (pintype "passive"))
      (node (ref "CH9") (pin "2") (pinfunction "2_2") (pintype "passive"))
    )
    (net (code "79") (name "VBAT_S") (class "Default")
      (node (ref "R29") (pin "1") (pinfunction "1_1") (pintype "passive"))
      (node (ref "R30") (pin "1") (pinfunction "1_1") (pintype "passive"))
      (node (ref "STM32F103RET6") (pin "26") (pinfunction "PB0_26") (pintype "bidirectional"))
    )
    (net (code "80") (name "VCC") (class "Default")
      (node (ref "C10") (pin "1") (pinfunction "1_1") (pintype "passive"))
      (node (ref "C12") (pin "1") (pinfunction "1_1") (pintype "passive"))
      (node (ref "C13") (pin "1") (pinfunction "1_1") (pintype "passive"))
      (node (ref "C14") (pin "1") (pinfunction "1_1") (pintype "passive"))
      (node (ref "C15") (pin "1") (pinfunction "1_1") (pintype "passive"))
      (node (ref "C17") (pin "1") (pinfunction "1_1") (pintype "passive"))
      (node (ref "C18") (pin "1") (pinfunction "1_1") (pintype "passive"))
      (node (ref "C20") (pin "1") (pinfunction "1_1") (pintype "passive"))
      (node (ref "C4") (pin "2") (pinfunction "2_2") (pintype "passive"))
      (node (ref "C6") (pin "1") (pinfunction "1_1") (pintype "passive"))
      (node (ref "FCM1608-0603") (pin "1") (pinfunction "P$1_1") (pintype "bidirectional"))
      (node (ref "HALL1") (pin "1") (pinfunction "S_1") (pintype "passive"))
      (node (ref "HALL2") (pin "1") (pinfunction "S_1") (pintype "passive"))
      (node (ref "IC1") (pin "2") (pinfunction "VOUT_2") (pintype "power_in"))
      (node (ref "IC1") (pin "4") (pinfunction "VOUT_4") (pintype "power_in"))
      (node (ref "IMU_DROTEK") (pin "1") (pinfunction "S_1") (pintype "passive"))
      (node (ref "I_T_V") (pin "4") (pinfunction "S_4") (pintype "passive"))
      (node (ref "MAXSONAR") (pin "2") (pinfunction "S_2") (pintype "passive"))
      (node (ref "NRF24L01+") (pin "2") (pinfunction "2_2") (pintype "passive"))
      (node (ref "R11") (pin "2") (pinfunction "2_2") (pintype "passive"))
      (node (ref "R17") (pin "1") (pinfunction "1_1") (pintype "passive"))
      (node (ref "R18") (pin "1") (pinfunction "1_1") (pintype "passive"))
      (node (ref "R20") (pin "2") (pinfunction "2_2") (pintype "passive"))
      (node (ref "R22") (pin "1") (pinfunction "1_1") (pintype "passive"))
      (node (ref "R23") (pin "1") (pinfunction "1_1") (pintype "passive"))
      (node (ref "R3") (pin "1") (pinfunction "1_1") (pintype "passive"))
      (node (ref "R9") (pin "1") (pinfunction "1_1") (pintype "passive"))
      (node (ref "STM32F103RET6") (pin "1") (pinfunction "VBAT_1") (pintype "power_in"))
      (node (ref "STM32F103RET6") (pin "19") (pinfunction "VDD_4_19") (pintype "power_in"))
      (node (ref "STM32F103RET6") (pin "32") (pinfunction "VDD_1_32") (pintype "power_in"))
      (node (ref "STM32F103RET6") (pin "48") (pinfunction "VDD_2_48") (pintype "power_in"))
      (node (ref "STM32F103RET6") (pin "64") (pinfunction "VDD_3_64") (pintype "power_in"))
      (node (ref "SWD") (pin "1") (pinfunction "S_1") (pintype "passive"))
      (node (ref "U$3") (pin "5") (pinfunction "VCC_5") (pintype "bidirectional"))
    )
    (net (code "81") (name "VDD") (class "Default")
      (node (ref "BAT60JFILM") (pin "C") (pinfunction "C_C") (pintype "passive"))
      (node (ref "IC1") (pin "3") (pinfunction "VIN_3") (pintype "input"))
      (node (ref "NL-652ETTL") (pin "1") (pinfunction "S_1") (pintype "passive"))
    )
    (net (code "82") (name "unconnected-(STM32F103RET6B-PA11-Pad44)") (class "Default")
      (node (ref "STM32F103RET6") (pin "44") (pinfunction "PA11_44") (pintype "bidirectional"))
    )
    (net (code "83") (name "unconnected-(STM32F103RET6B-PA15-Pad50)") (class "Default")
      (node (ref "STM32F103RET6") (pin "50") (pinfunction "PA15_50") (pintype "bidirectional"))
    )
    (net (code "84") (name "unconnected-(STM32F103RET6F-PC13-Pad2)") (class "Default")
      (node (ref "STM32F103RET6") (pin "2") (pinfunction "PC13_2") (pintype "bidirectional"))
    )
    (net (code "85") (name "unconnected-(STM32F103RET6F-PC14-Pad3)") (class "Default")
      (node (ref "STM32F103RET6") (pin "3") (pinfunction "PC14_3") (pintype "bidirectional"))
    )
    (net (code "86") (name "unconnected-(STM32F103RET6F-PC15-Pad4)") (class "Default")
      (node (ref "STM32F103RET6") (pin "4") (pinfunction "PC15_4") (pintype "bidirectional"))
    )
    (net (code "87") (name "unconnected-(STM32F103RET6G-PC0-Pad8)") (class "Default")
      (node (ref "STM32F103RET6") (pin "8") (pinfunction "PC0_8") (pintype "bidirectional"))
    )
    (net (code "88") (name "unconnected-(STM32F103RET6G-PC3-Pad11)") (class "Default")
      (node (ref "STM32F103RET6") (pin "11") (pinfunction "PC3_11") (pintype "bidirectional"))
    )
    (net (code "89") (name "unconnected-(STM32F103RET6G-PC5-Pad25)") (class "Default")
      (node (ref "STM32F103RET6") (pin "25") (pinfunction "PC5_25") (pintype "bidirectional"))
    )
    (net (code "90") (name "unconnected-(STM32F103RET6H-PD2-Pad54)") (class "Default")
      (node (ref "STM32F103RET6") (pin "54") (pinfunction "PD2_54") (pintype "bidirectional"))
    )
    (net (code "91") (name "unconnected-(U$3-GPIO2-Pad8)") (class "Default")
      (node (ref "U$3") (pin "8") (pinfunction "GPIO2_8") (pintype "bidirectional"))
    )
  )
)
